# design.net
KiCad netlist of a schematic drawn in EasyEDA Pro
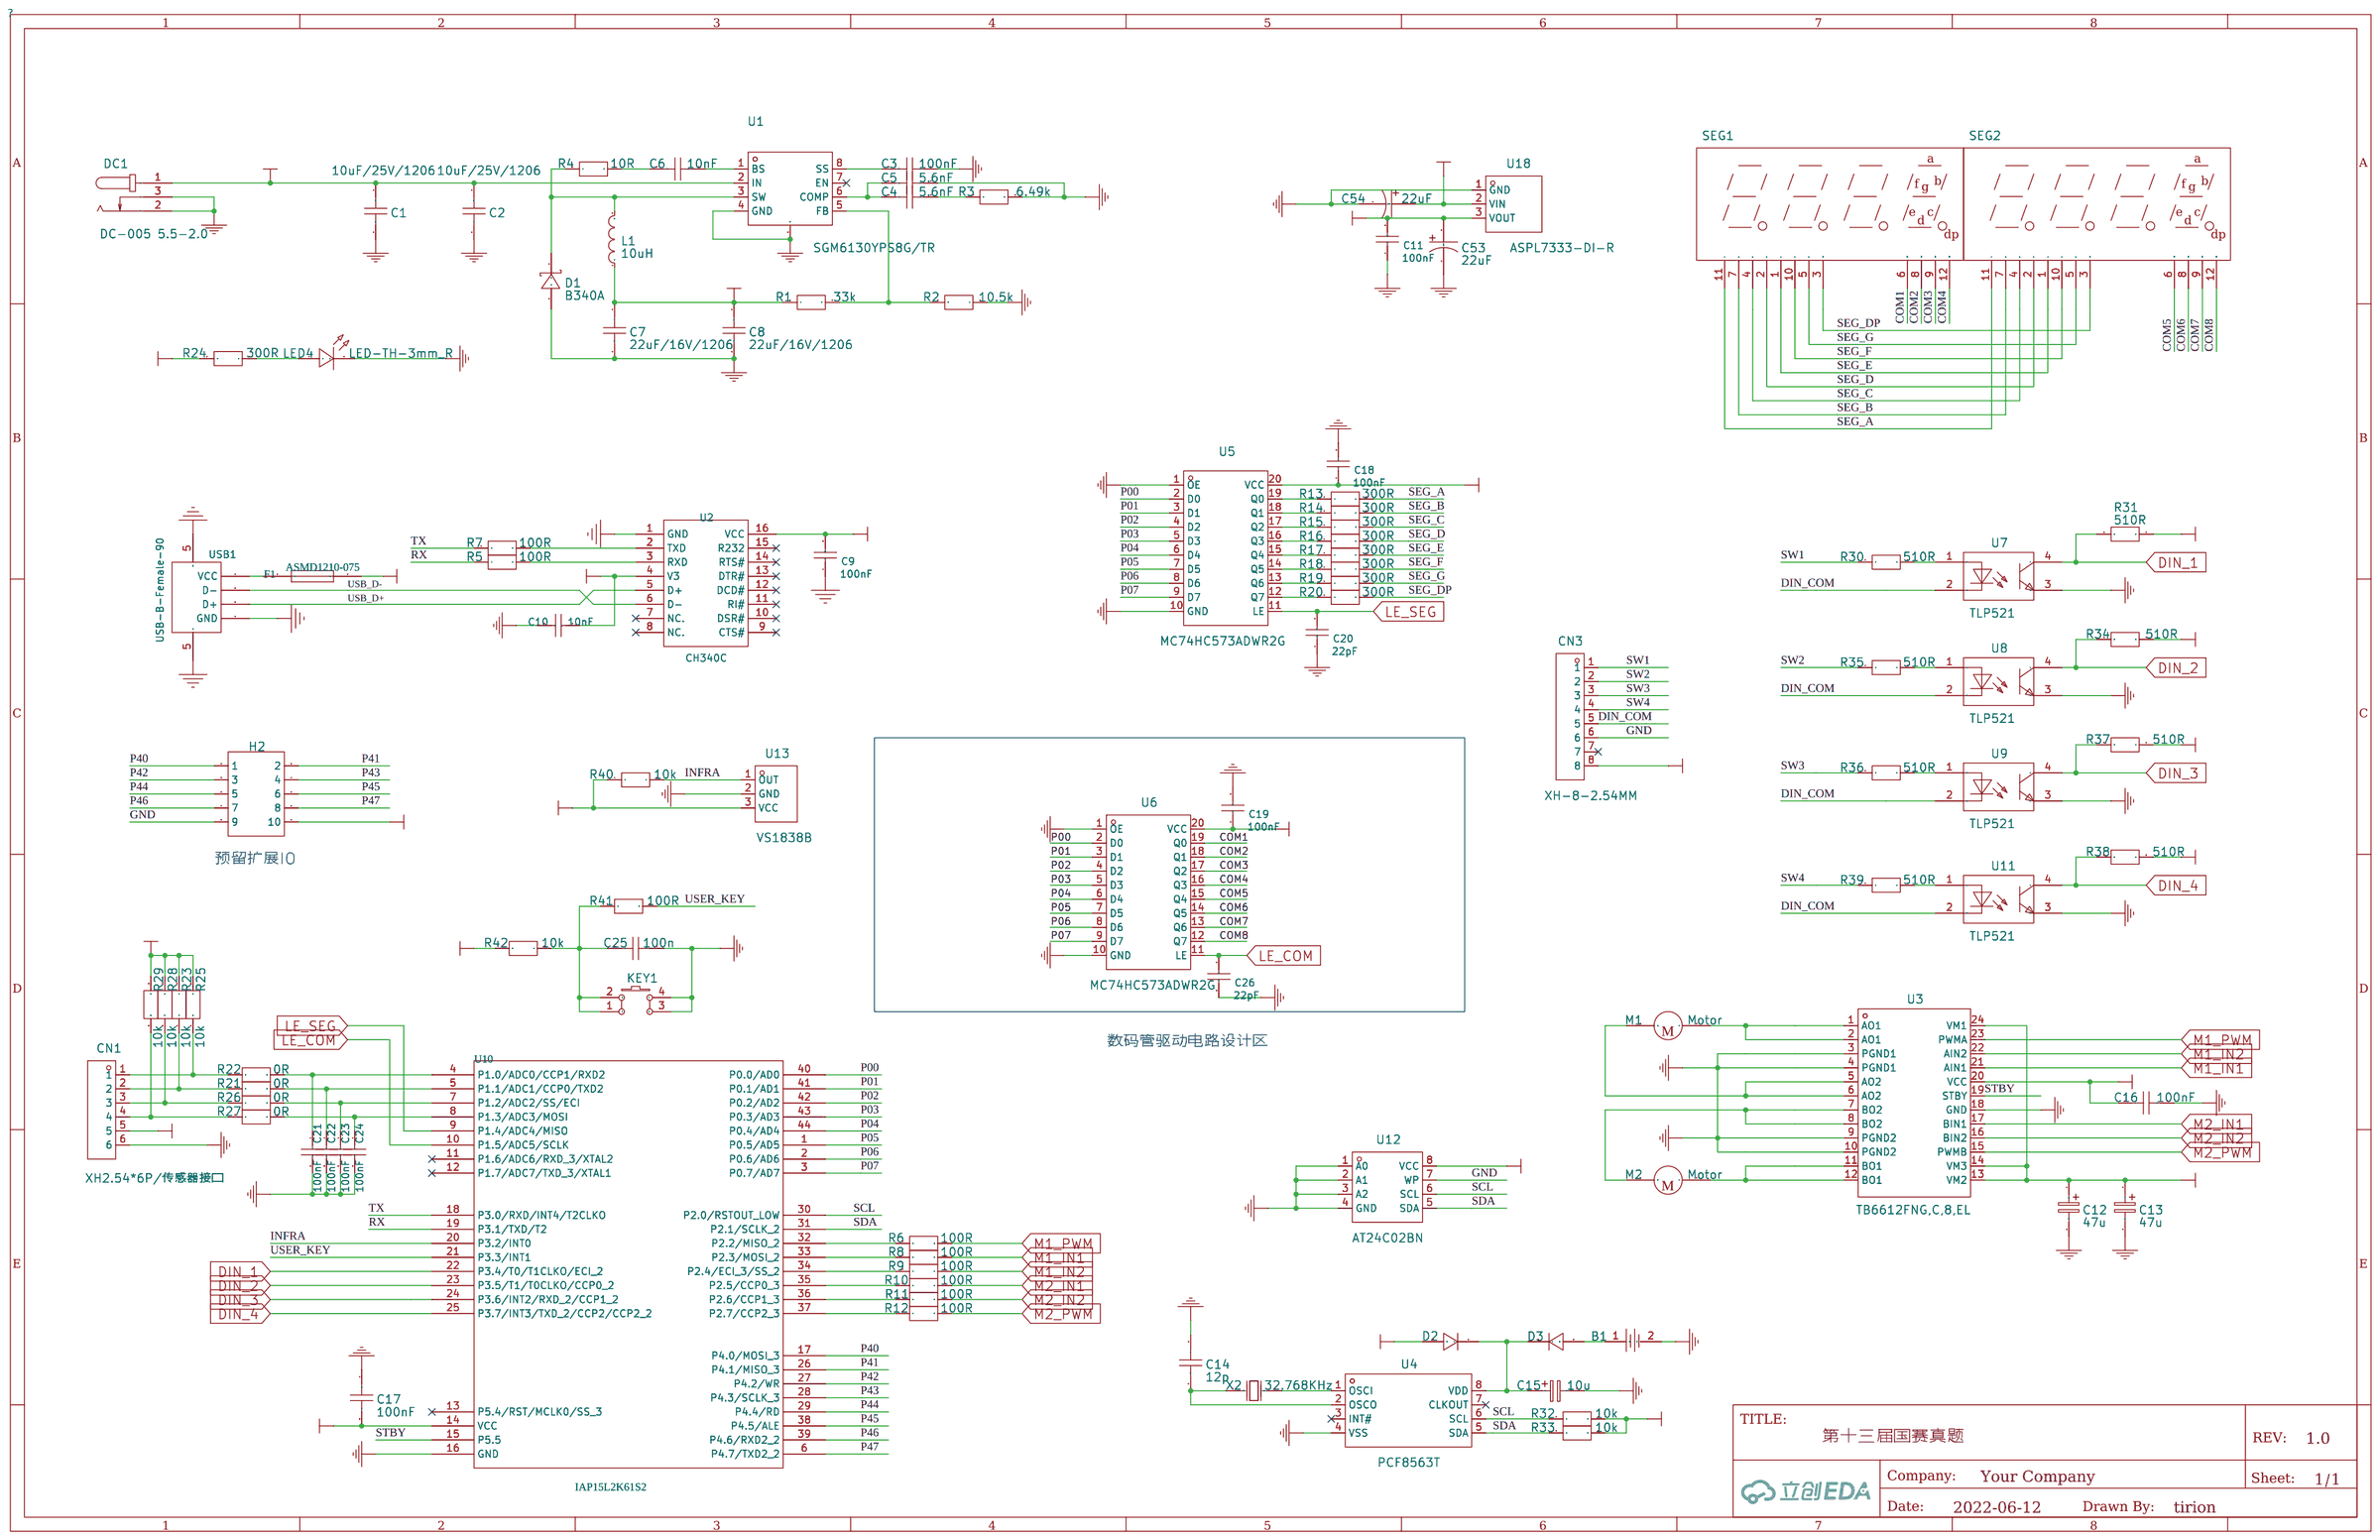
[diagram p0: schematic sheet]

(export (version "E")
  (design (tool "Eeschema 10.0.6"))
  (components
    (comp (ref "B1")
      (value "CR1220-2")
      (fields (field (name "Manufacturer") "Q&amp;J"))
      (libsource (lib "easyedapro") (part "CR1220-2"))
    )
    (comp (ref "C1") (value "10uF/25V/1206") (libsource (lib "easyedapro") (part "10uF/25V/1206")))
    (comp (ref "C2") (value "10uF/25V/1206") (libsource (lib "easyedapro") (part "10uF/25V/1206")))
    (comp (ref "C3") (value "100nF") (libsource (lib "") (part "100nF_1")))
    (comp (ref "C4") (value "5.6nF") (libsource (lib "easyedapro") (part "5.6nF")))
    (comp (ref "C5") (value "5.6nF") (libsource (lib "easyedapro") (part "5.6nF")))
    (comp (ref "C6") (value "10nF") (libsource (lib "easyedapro") (part "10nF")))
    (comp (ref "C7") (value "22uF/16V/1206") (libsource (lib "easyedapro") (part "22uF/16V/1206")))
    (comp (ref "C8") (value "22uF/16V/1206") (libsource (lib "easyedapro") (part "22uF/16V/1206")))
    (comp (ref "C9")
      (value "100nF")
      (fields (field (name "Manufacturer Part") "0805F104M500NT") (field (name "Manufacturer") "FH"))
      (libsource (lib "easyedapro") (part "100nF"))
    )
    (comp (ref "C10")
      (value "10nF")
      (fields (field (name "Manufacturer Part") "0805F104M500NT") (field (name "Manufacturer") "FH"))
      (libsource (lib "easyedapro") (part "100nF"))
    )
    (comp (ref "C11")
      (value "100nF")
      (fields (field (name "Manufacturer Part") "0805F104M500NT") (field (name "Manufacturer") "FH"))
      (libsource (lib "easyedapro") (part "100nF"))
    )
    (comp (ref "C12") (value "47u") (libsource (lib "easyedapro") (part "47u")))
    (comp (ref "C13") (value "47u") (libsource (lib "easyedapro") (part "47u")))
    (comp (ref "C14") (value "12p") (libsource (lib "easyedapro") (part "12p")))
    (comp (ref "C15") (value "10u") (libsource (lib "easyedapro") (part "10u")))
    (comp (ref "C16") (value "100nF") (libsource (lib "") (part "100nF_1")))
    (comp (ref "C17") (value "100nF") (libsource (lib "") (part "100nF_1")))
    (comp (ref "C18")
      (value "100nF")
      (fields (field (name "Manufacturer Part") "0805F104M500NT") (field (name "Manufacturer") "FH"))
      (libsource (lib "easyedapro") (part "100nF"))
    )
    (comp (ref "C19")
      (value "100nF")
      (fields (field (name "Manufacturer Part") "0805F104M500NT") (field (name "Manufacturer") "FH"))
      (libsource (lib "easyedapro") (part "100nF"))
    )
    (comp (ref "C20")
      (value "22pF")
      (fields (field (name "Manufacturer Part") "0805F104M500NT") (field (name "Manufacturer") "FH"))
      (libsource (lib "easyedapro") (part "100nF"))
    )
    (comp (ref "C21")
      (value "100nF")
      (fields (field (name "Manufacturer Part") "0805F104M500NT") (field (name "Manufacturer") "FH"))
      (libsource (lib "easyedapro") (part "100nF"))
    )
    (comp (ref "C22")
      (value "100nF")
      (fields (field (name "Manufacturer Part") "0805F104M500NT") (field (name "Manufacturer") "FH"))
      (libsource (lib "easyedapro") (part "100nF"))
    )
    (comp (ref "C23")
      (value "100nF")
      (fields (field (name "Manufacturer Part") "0805F104M500NT") (field (name "Manufacturer") "FH"))
      (libsource (lib "easyedapro") (part "100nF"))
    )
    (comp (ref "C24")
      (value "100nF")
      (fields (field (name "Manufacturer Part") "0805F104M500NT") (field (name "Manufacturer") "FH"))
      (libsource (lib "easyedapro") (part "100nF"))
    )
    (comp (ref "C25") (value "100n") (libsource (lib "easyedapro") (part "100n")))
    (comp (ref "C26")
      (value "22pF")
      (fields (field (name "Manufacturer Part") "0805F104M500NT") (field (name "Manufacturer") "FH"))
      (libsource (lib "easyedapro") (part "100nF"))
    )
    (comp (ref "C53")
      (value "22uF")
      (fields (field (name "Manufacturer") "HonorElec"))
      (libsource (lib "easyedapro") (part "22uF"))
    )
    (comp (ref "C54")
      (value "22uF")
      (fields (field (name "Manufacturer") "HonorElec"))
      (libsource (lib "easyedapro") (part "22uF"))
    )
    (comp (ref "CN1")
      (value "XH2.54*6P/传感器接口")
      (fields (field (name "Manufacturer Part") "XH2.54*6P_直插"))
      (libsource (lib "easyedapro") (part "XH2.54*6P/传感器接口"))
    )
    (comp (ref "CN3") (value "XH-8-2.54MM") (libsource (lib "easyedapro") (part "XH-8-2.54MM")))
    (comp (ref "D1")
      (value "B340A")
      (fields (field (name "Manufacturer") "MDD"))
      (libsource (lib "easyedapro") (part "B340A"))
    )
    (comp (ref "D2")
      (value "1N4148")
      (fields (field (name "Manufacturer") "STMicroelectronics"))
      (libsource (lib "easyedapro") (part "1N4148"))
    )
    (comp (ref "D3")
      (value "1N4148")
      (fields (field (name "Manufacturer") "STMicroelectronics"))
      (libsource (lib "easyedapro") (part "1N4148"))
    )
    (comp (ref "DC1")
      (value "DC-005 5.5-2.0")
      (fields (field (name "Manufacturer") "ShenzhenCankemeng"))
      (libsource (lib "easyedapro") (part "DC-005 5.5-2.0"))
    )
    (comp (ref "F1")
      (value "ASMD1210-075")
      (fields (field (name "Publisher") "Altium Limited"))
      (libsource (lib "easyedapro") (part "ASMD1210-075"))
    )
    (comp (ref "H2") (value "HDR-F-2.54_2x5") (libsource (lib "easyedapro") (part "HDR-F-2.54_2x5")))
    (comp (ref "KEY1")
      (value "K4-6×6_SMD")
      (fields (field (name "Manufacturer Part") "K2-6639SP-D4SC-04") (field (name "Manufacturer") "韩国韩荣"))
      (libsource (lib "easyedapro") (part "K4-6×6_SMD"))
    )
    (comp (ref "L1")
      (value "10uH")
      (fields
        (field (name "Manufacturer Part") "1217AS-H-100M=P3")
        (field (name "Manufacturer") "MurataElectronics")
      )
      (libsource (lib "easyedapro") (part "10uH"))
    )
    (comp (ref "LED4")
      (value "LED-TH-3mm_R")
      (fields
        (field (name "Manufacturer Part") "204-10SDRD/S530-A3-L")
        (field (name "Manufacturer") "EVERLIGHT(台湾亿光)")
      )
      (libsource (lib "easyedapro") (part "LED-TH-3mm_R"))
    )
    (comp (ref "M1") (value "Motor") (libsource (lib "easyedapro") (part "Motor")))
    (comp (ref "M2") (value "Motor") (libsource (lib "easyedapro") (part "Motor")))
    (comp (ref "R1") (value "33k") (libsource (lib "easyedapro") (part "33k")))
    (comp (ref "R2") (value "10.5k") (libsource (lib "easyedapro") (part "10.5k")))
    (comp (ref "R3") (value "6.49k") (libsource (lib "easyedapro") (part "6.49k")))
    (comp (ref "R4") (value "10R") (libsource (lib "easyedapro") (part "10R")))
    (comp (ref "R5") (value "100R") (libsource (lib "easyedapro") (part "100R")))
    (comp (ref "R6") (value "100R") (libsource (lib "easyedapro") (part "100R")))
    (comp (ref "R7") (value "100R") (libsource (lib "easyedapro") (part "100R")))
    (comp (ref "R8") (value "100R") (libsource (lib "easyedapro") (part "100R")))
    (comp (ref "R9") (value "100R") (libsource (lib "easyedapro") (part "100R")))
    (comp (ref "R10") (value "100R") (libsource (lib "easyedapro") (part "100R")))
    (comp (ref "R11") (value "100R") (libsource (lib "easyedapro") (part "100R")))
    (comp (ref "R12") (value "100R") (libsource (lib "easyedapro") (part "100R")))
    (comp (ref "R13") (value "300R") (libsource (lib "easyedapro") (part "300R")))
    (comp (ref "R14") (value "300R") (libsource (lib "easyedapro") (part "300R")))
    (comp (ref "R15") (value "300R") (libsource (lib "easyedapro") (part "300R")))
    (comp (ref "R16") (value "300R") (libsource (lib "easyedapro") (part "300R")))
    (comp (ref "R17") (value "300R") (libsource (lib "easyedapro") (part "300R")))
    (comp (ref "R18") (value "300R") (libsource (lib "easyedapro") (part "300R")))
    (comp (ref "R19") (value "300R") (libsource (lib "easyedapro") (part "300R")))
    (comp (ref "R20") (value "300R") (libsource (lib "easyedapro") (part "300R")))
    (comp (ref "R21") (value "0R") (libsource (lib "easyedapro") (part "0R")))
    (comp (ref "R22") (value "0R") (libsource (lib "easyedapro") (part "0R")))
    (comp (ref "R23") (value "10k") (libsource (lib "easyedapro") (part "10k")))
    (comp (ref "R24") (value "300R") (libsource (lib "easyedapro") (part "300R")))
    (comp (ref "R25") (value "10k") (libsource (lib "easyedapro") (part "10k")))
    (comp (ref "R26") (value "0R") (libsource (lib "easyedapro") (part "0R")))
    (comp (ref "R27") (value "0R") (libsource (lib "easyedapro") (part "0R")))
    (comp (ref "R28") (value "10k") (libsource (lib "easyedapro") (part "10k")))
    (comp (ref "R29") (value "10k") (libsource (lib "easyedapro") (part "10k")))
    (comp (ref "R30") (value "510R") (libsource (lib "easyedapro") (part "510R")))
    (comp (ref "R31") (value "510R") (libsource (lib "easyedapro") (part "510R")))
    (comp (ref "R32") (value "10k") (libsource (lib "easyedapro") (part "10k")))
    (comp (ref "R33") (value "10k") (libsource (lib "easyedapro") (part "10k")))
    (comp (ref "R34") (value "510R") (libsource (lib "easyedapro") (part "510R")))
    (comp (ref "R35") (value "510R") (libsource (lib "easyedapro") (part "510R")))
    (comp (ref "R36") (value "510R") (libsource (lib "easyedapro") (part "510R")))
    (comp (ref "R37") (value "510R") (libsource (lib "easyedapro") (part "510R")))
    (comp (ref "R38") (value "510R") (libsource (lib "easyedapro") (part "510R")))
    (comp (ref "R39") (value "510R") (libsource (lib "easyedapro") (part "510R")))
    (comp (ref "R40") (value "10k") (libsource (lib "easyedapro") (part "10k")))
    (comp (ref "R41") (value "100R") (libsource (lib "easyedapro") (part "100R")))
    (comp (ref "R42") (value "10k") (libsource (lib "easyedapro") (part "10k")))
    (comp (ref "SEG1")
      (value "0.36寸4位数码管")
      (fields (field (name "Manufacturer Part") "FJ5461BH纯红") (field (name "Manufacturer") "ReliaPro"))
      (libsource (lib "easyedapro") (part "0.36寸4位数码管"))
    )
    (comp (ref "SEG2")
      (value "0.36寸4位数码管")
      (fields (field (name "Manufacturer Part") "FJ5461BH纯红") (field (name "Manufacturer") "ReliaPro"))
      (libsource (lib "easyedapro") (part "0.36寸4位数码管"))
    )
    (comp (ref "U1")
      (value "SGM6130YPS8G/TR")
      (fields (field (name "Manufacturer") "SGMICRO"))
      (libsource (lib "easyedapro") (part "SGM6130YPS8G/TR"))
    )
    (comp (ref "U2")
      (value "CH340C")
      (fields (field (name "Manufacturer") "WCH"))
      (libsource (lib "easyedapro") (part "CH340C"))
    )
    (comp (ref "U3")
      (value "TB6612FNG,C,8,EL")
      (fields (field (name "Manufacturer") "TOSHIBA"))
      (libsource (lib "easyedapro") (part "TB6612FNG,C,8,EL"))
    )
    (comp (ref "U4")
      (value "PCF8563T")
      (fields (field (name "Manufacturer Part") "PCF8563T/5,518") (field (name "Manufacturer") "NXP"))
      (libsource (lib "easyedapro") (part "PCF8563T"))
    )
    (comp (ref "U5")
      (value "MC74HC573ADWR2G")
      (fields (field (name "Manufacturer") "ONSemicon"))
      (libsource (lib "easyedapro") (part "MC74HC573ADWR2G"))
    )
    (comp (ref "U6")
      (value "MC74HC573ADWR2G")
      (fields (field (name "Manufacturer") "ONSemicon"))
      (libsource (lib "easyedapro") (part "MC74HC573ADWR2G"))
    )
    (comp (ref "U7") (value "TLP521") (libsource (lib "easyedapro") (part "TLP521")))
    (comp (ref "U8") (value "TLP521") (libsource (lib "easyedapro") (part "TLP521")))
    (comp (ref "U9") (value "TLP521") (libsource (lib "easyedapro") (part "TLP521")))
    (comp (ref "U10") (value "IAP15L2K61S2") (libsource (lib "easyedapro") (part "IAP15L2K61S2")))
    (comp (ref "U11") (value "TLP521") (libsource (lib "easyedapro") (part "TLP521")))
    (comp (ref "U12") (value "AT24C02BN") (libsource (lib "easyedapro") (part "AT24C02BN")))
    (comp (ref "U13") (value "VS1838B") (libsource (lib "easyedapro") (part "VS1838B")))
    (comp (ref "U18")
      (value "ASPL7333-DI-R")
      (fields (field (name "Manufacturer") "Ascend(安森德)"))
      (libsource (lib "easyedapro") (part "ASPL7333-DI-R"))
    )
    (comp (ref "USB1")
      (value "USB-B-Female-90")
      (fields (field (name "Manufacturer Part") "USB-BF90") (field (name "Manufacturer") "ValuePro"))
      (libsource (lib "easyedapro") (part "USB-B-Female-90"))
    )
    (comp (ref "X2")
      (value "32.768KHz")
      (fields
        (field (name "Manufacturer Part") "6K832768F12UB")
        (field (name "Manufacturer") "SHENZHENCRYSTALTECH")
      )
      (libsource (lib "easyedapro") (part "32.768KHz"))
    )
  )
  (nets
    (net (code "1") (name "+3V3") (class "Default")
      (node (ref "C10") (pin "1") (pinfunction "1_1") (pintype "input"))
      (node (ref "C11") (pin "2") (pinfunction "2_2") (pintype "input"))
      (node (ref "C16") (pin "1") (pinfunction "1_1") (pintype "input"))
      (node (ref "C17") (pin "2") (pinfunction "2_2") (pintype "input"))
      (node (ref "C18") (pin "1") (pinfunction "1_1") (pintype "input"))
      (node (ref "C19") (pin "1") (pinfunction "1_1") (pintype "input"))
      (node (ref "C53") (pin "1") (pinfunction "1_1") (pintype "input"))
      (node (ref "C7") (pin "1") (pinfunction "1_1") (pintype "input"))
      (node (ref "C8") (pin "1") (pinfunction "1_1") (pintype "input"))
      (node (ref "C9") (pin "2") (pinfunction "2_2") (pintype "input"))
      (node (ref "CN1") (pin "5") (pinfunction "5_5") (pintype "input"))
      (node (ref "D2") (pin "2") (pinfunction "2_2") (pintype "input"))
      (node (ref "H2") (pin "10") (pinfunction "10_10") (pintype "input"))
      (node (ref "L1") (pin "1") (pinfunction "1_1") (pintype "input"))
      (node (ref "R1") (pin "1") (pinfunction "1_1") (pintype "input"))
      (node (ref "R23") (pin "1") (pinfunction "1_1") (pintype "input"))
      (node (ref "R24") (pin "2") (pinfunction "2_2") (pintype "input"))
      (node (ref "R25") (pin "1") (pinfunction "1_1") (pintype "input"))
      (node (ref "R28") (pin "1") (pinfunction "1_1") (pintype "input"))
      (node (ref "R29") (pin "1") (pinfunction "1_1") (pintype "input"))
      (node (ref "R31") (pin "1") (pinfunction "1_1") (pintype "input"))
      (node (ref "R32") (pin "2") (pinfunction "2_2") (pintype "input"))
      (node (ref "R33") (pin "2") (pinfunction "2_2") (pintype "input"))
      (node (ref "R34") (pin "1") (pinfunction "1_1") (pintype "input"))
      (node (ref "R37") (pin "1") (pinfunction "1_1") (pintype "input"))
      (node (ref "R38") (pin "1") (pinfunction "1_1") (pintype "input"))
      (node (ref "R40") (pin "1") (pinfunction "1_1") (pintype "input"))
      (node (ref "R42") (pin "2") (pinfunction "2_2") (pintype "input"))
      (node (ref "U10") (pin "14") (pinfunction "VCC_14") (pintype "input"))
      (node (ref "U12") (pin "8") (pinfunction "VCC_8") (pintype "input"))
      (node (ref "U13") (pin "3") (pinfunction "VCC_3") (pintype "input"))
      (node (ref "U18") (pin "3") (pinfunction "VOUT_3") (pintype "input"))
      (node (ref "U2") (pin "16") (pinfunction "VCC_16") (pintype "input"))
      (node (ref "U2") (pin "4") (pinfunction "V3_4") (pintype "input"))
      (node (ref "U3") (pin "20") (pinfunction "VCC_20") (pintype "input"))
      (node (ref "U5") (pin "20") (pinfunction "VCC_20") (pintype "input"))
      (node (ref "U6") (pin "20") (pinfunction "VCC_20") (pintype "input"))
    )
    (net (code "2") (name "/COM1") (class "Default")
      (node (ref "SEG1") (pin "6") (pinfunction "DIG4_6") (pintype "input"))
      (node (ref "U6") (pin "19") (pinfunction "Q0_19") (pintype "input"))
    )
    (net (code "3") (name "/COM2") (class "Default")
      (node (ref "SEG1") (pin "8") (pinfunction "DIG3_8") (pintype "input"))
      (node (ref "U6") (pin "18") (pinfunction "Q1_18") (pintype "input"))
    )
    (net (code "4") (name "/COM3") (class "Default")
      (node (ref "SEG1") (pin "9") (pinfunction "DIG2_9") (pintype "input"))
      (node (ref "U6") (pin "17") (pinfunction "Q2_17") (pintype "input"))
    )
    (net (code "5") (name "/COM4") (class "Default")
      (node (ref "SEG1") (pin "12") (pinfunction "DIG1_12") (pintype "input"))
      (node (ref "U6") (pin "16") (pinfunction "Q3_16") (pintype "input"))
    )
    (net (code "6") (name "/COM5") (class "Default")
      (node (ref "SEG2") (pin "6") (pinfunction "DIG4_6") (pintype "input"))
      (node (ref "U6") (pin "15") (pinfunction "Q4_15") (pintype "input"))
    )
    (net (code "7") (name "/COM6") (class "Default")
      (node (ref "SEG2") (pin "8") (pinfunction "DIG3_8") (pintype "input"))
      (node (ref "U6") (pin "14") (pinfunction "Q5_14") (pintype "input"))
    )
    (net (code "8") (name "/COM7") (class "Default")
      (node (ref "SEG2") (pin "9") (pinfunction "DIG2_9") (pintype "input"))
      (node (ref "U6") (pin "13") (pinfunction "Q6_13") (pintype "input"))
    )
    (net (code "9") (name "/COM8") (class "Default")
      (node (ref "SEG2") (pin "12") (pinfunction "DIG1_12") (pintype "input"))
      (node (ref "U6") (pin "12") (pinfunction "Q7_12") (pintype "input"))
    )
    (net (code "10") (name "/DIN_COM") (class "Default")
      (node (ref "CN3") (pin "5") (pinfunction "5_5") (pintype "input"))
      (node (ref "U11") (pin "2") (pinfunction "2_2") (pintype "input"))
      (node (ref "U7") (pin "2") (pinfunction "2_2") (pintype "input"))
      (node (ref "U8") (pin "2") (pinfunction "2_2") (pintype "input"))
      (node (ref "U9") (pin "2") (pinfunction "2_2") (pintype "input"))
    )
    (net (code "11") (name "/INFRA") (class "Default")
      (node (ref "R40") (pin "2") (pinfunction "2_2") (pintype "input"))
      (node (ref "U10") (pin "20") (pinfunction "P3.2/INT0_20") (pintype "input"))
      (node (ref "U13") (pin "1") (pinfunction "OUT_1") (pintype "input"))
    )
    (net (code "12") (name "/P00") (class "Default")
      (node (ref "U10") (pin "40") (pinfunction "P0.0/AD0_40") (pintype "bidirectional"))
      (node (ref "U5") (pin "2") (pinfunction "D0_2") (pintype "input"))
      (node (ref "U6") (pin "2") (pinfunction "D0_2") (pintype "input"))
    )
    (net (code "13") (name "/P01") (class "Default")
      (node (ref "U10") (pin "41") (pinfunction "P0.1/AD1_41") (pintype "bidirectional"))
      (node (ref "U5") (pin "3") (pinfunction "D1_3") (pintype "input"))
      (node (ref "U6") (pin "3") (pinfunction "D1_3") (pintype "input"))
    )
    (net (code "14") (name "/P02") (class "Default")
      (node (ref "U10") (pin "42") (pinfunction "P0.2/AD2_42") (pintype "bidirectional"))
      (node (ref "U5") (pin "4") (pinfunction "D2_4") (pintype "input"))
      (node (ref "U6") (pin "4") (pinfunction "D2_4") (pintype "input"))
    )
    (net (code "15") (name "/P03") (class "Default")
      (node (ref "U10") (pin "43") (pinfunction "P0.3/AD3_43") (pintype "bidirectional"))
      (node (ref "U5") (pin "5") (pinfunction "D3_5") (pintype "input"))
      (node (ref "U6") (pin "5") (pinfunction "D3_5") (pintype "input"))
    )
    (net (code "16") (name "/P04") (class "Default")
      (node (ref "U10") (pin "44") (pinfunction "P0.4/AD4_44") (pintype "bidirectional"))
      (node (ref "U5") (pin "6") (pinfunction "D4_6") (pintype "input"))
      (node (ref "U6") (pin "6") (pinfunction "D4_6") (pintype "input"))
    )
    (net (code "17") (name "/P05") (class "Default")
      (node (ref "U10") (pin "1") (pinfunction "P0.5/AD5_1") (pintype "bidirectional"))
      (node (ref "U5") (pin "7") (pinfunction "D5_7") (pintype "input"))
      (node (ref "U6") (pin "7") (pinfunction "D5_7") (pintype "input"))
    )
    (net (code "18") (name "/P06") (class "Default")
      (node (ref "U10") (pin "2") (pinfunction "P0.6/AD6_2") (pintype "bidirectional"))
      (node (ref "U5") (pin "8") (pinfunction "D6_8") (pintype "input"))
      (node (ref "U6") (pin "8") (pinfunction "D6_8") (pintype "input"))
    )
    (net (code "19") (name "/P07") (class "Default")
      (node (ref "U10") (pin "3") (pinfunction "P0.7/AD7_3") (pintype "bidirectional"))
      (node (ref "U5") (pin "9") (pinfunction "D7_9") (pintype "input"))
      (node (ref "U6") (pin "9") (pinfunction "D7_9") (pintype "input"))
    )
    (net (code "20") (name "/P40") (class "Default")
      (node (ref "H2") (pin "1") (pinfunction "1_1") (pintype "input"))
      (node (ref "U10") (pin "17") (pinfunction "P4.0/MOSI_3_17") (pintype "bidirectional"))
    )
    (net (code "21") (name "/P41") (class "Default")
      (node (ref "H2") (pin "2") (pinfunction "2_2") (pintype "input"))
      (node (ref "U10") (pin "26") (pinfunction "P4.1/MISO_3_26") (pintype "bidirectional"))
    )
    (net (code "22") (name "/P42") (class "Default")
      (node (ref "H2") (pin "3") (pinfunction "3_3") (pintype "input"))
      (node (ref "U10") (pin "27") (pinfunction "P4.2/WR_27") (pintype "input"))
    )
    (net (code "23") (name "/P43") (class "Default")
      (node (ref "H2") (pin "4") (pinfunction "4_4") (pintype "input"))
      (node (ref "U10") (pin "28") (pinfunction "P4.3/SCLK_3_28") (pintype "bidirectional"))
    )
    (net (code "24") (name "/P44") (class "Default")
      (node (ref "H2") (pin "5") (pinfunction "5_5") (pintype "input"))
      (node (ref "U10") (pin "29") (pinfunction "P4.4/RD_29") (pintype "input"))
    )
    (net (code "25") (name "/P45") (class "Default")
      (node (ref "H2") (pin "6") (pinfunction "6_6") (pintype "input"))
      (node (ref "U10") (pin "38") (pinfunction "P4.5/ALE_38") (pintype "input"))
    )
    (net (code "26") (name "/P46") (class "Default")
      (node (ref "H2") (pin "7") (pinfunction "7_7") (pintype "input"))
      (node (ref "U10") (pin "39") (pinfunction "P4.6/RXD2_2_39") (pintype "input"))
    )
    (net (code "27") (name "/P47") (class "Default")
      (node (ref "H2") (pin "8") (pinfunction "8_8") (pintype "input"))
      (node (ref "U10") (pin "6") (pinfunction "P4.7/TXD2_2_6") (pintype "bidirectional"))
    )
    (net (code "28") (name "/RX") (class "Default")
      (node (ref "R5") (pin "1") (pinfunction "1_1") (pintype "input"))
      (node (ref "U10") (pin "19") (pinfunction "P3.1/TXD/T2_19") (pintype "input"))
    )
    (net (code "29") (name "/SCL") (class "Default")
      (node (ref "R32") (pin "1") (pinfunction "1_1") (pintype "input"))
      (node (ref "U10") (pin "30") (pinfunction "P2.0/RSTOUT_LOW_30") (pintype "bidirectional"))
      (node (ref "U12") (pin "6") (pinfunction "SCL_6") (pintype "input"))
      (node (ref "U4") (pin "6") (pinfunction "SCL_6") (pintype "input"))
    )
    (net (code "30") (name "/SDA") (class "Default")
      (node (ref "R33") (pin "1") (pinfunction "1_1") (pintype "input"))
      (node (ref "U10") (pin "31") (pinfunction "P2.1/SCLK_2_31") (pintype "bidirectional"))
      (node (ref "U12") (pin "5") (pinfunction "SDA_5") (pintype "input"))
      (node (ref "U4") (pin "5") (pinfunction "SDA_5") (pintype "input"))
    )
    (net (code "31") (name "/SEG_A") (class "Default")
      (node (ref "R13") (pin "2") (pinfunction "2_2") (pintype "input"))
      (node (ref "SEG1") (pin "11") (pinfunction "A_11") (pintype "input"))
      (node (ref "SEG2") (pin "11") (pinfunction "A_11") (pintype "input"))
    )
    (net (code "32") (name "/SEG_B") (class "Default")
      (node (ref "R14") (pin "2") (pinfunction "2_2") (pintype "input"))
      (node (ref "SEG1") (pin "7") (pinfunction "B_7") (pintype "input"))
      (node (ref "SEG2") (pin "7") (pinfunction "B_7") (pintype "input"))
    )
    (net (code "33") (name "/SEG_C") (class "Default")
      (node (ref "R15") (pin "2") (pinfunction "2_2") (pintype "input"))
      (node (ref "SEG1") (pin "4") (pinfunction "C_4") (pintype "input"))
      (node (ref "SEG2") (pin "4") (pinfunction "C_4") (pintype "input"))
    )
    (net (code "34") (name "/SEG_D") (class "Default")
      (node (ref "R16") (pin "2") (pinfunction "2_2") (pintype "input"))
      (node (ref "SEG1") (pin "2") (pinfunction "D_2") (pintype "input"))
      (node (ref "SEG2") (pin "2") (pinfunction "D_2") (pintype "input"))
    )
    (net (code "35") (name "/SEG_DP") (class "Default")
      (node (ref "R20") (pin "2") (pinfunction "2_2") (pintype "input"))
      (node (ref "SEG1") (pin "3") (pinfunction "DP_3") (pintype "input"))
      (node (ref "SEG2") (pin "3") (pinfunction "DP_3") (pintype "input"))
    )
    (net (code "36") (name "/SEG_E") (class "Default")
      (node (ref "R17") (pin "2") (pinfunction "2_2") (pintype "input"))
      (node (ref "SEG1") (pin "1") (pinfunction "E_1") (pintype "input"))
      (node (ref "SEG2") (pin "1") (pinfunction "E_1") (pintype "input"))
    )
    (net (code "37") (name "/SEG_F") (class "Default")
      (node (ref "R18") (pin "2") (pinfunction "2_2") (pintype "input"))
      (node (ref "SEG1") (pin "10") (pinfunction "F_10") (pintype "input"))
      (node (ref "SEG2") (pin "10") (pinfunction "F_10") (pintype "input"))
    )
    (net (code "38") (name "/SEG_G") (class "Default")
      (node (ref "R19") (pin "2") (pinfunction "2_2") (pintype "input"))
      (node (ref "SEG1") (pin "5") (pinfunction "G_5") (pintype "input"))
      (node (ref "SEG2") (pin "5") (pinfunction "G_5") (pintype "input"))
    )
    (net (code "39") (name "/STBY") (class "Default")
      (node (ref "U10") (pin "15") (pinfunction "P5.5_15") (pintype "input"))
      (node (ref "U3") (pin "19") (pinfunction "STBY_19") (pintype "input"))
    )
    (net (code "40") (name "/SW1") (class "Default")
      (node (ref "CN3") (pin "1") (pinfunction "1_1") (pintype "input"))
      (node (ref "R30") (pin "1") (pinfunction "1_1") (pintype "input"))
    )
    (net (code "41") (name "/SW2") (class "Default")
      (node (ref "CN3") (pin "2") (pinfunction "2_2") (pintype "input"))
      (node (ref "R35") (pin "1") (pinfunction "1_1") (pintype "input"))
    )
    (net (code "42") (name "/SW3") (class "Default")
      (node (ref "CN3") (pin "3") (pinfunction "3_3") (pintype "input"))
      (node (ref "R36") (pin "1") (pinfunction "1_1") (pintype "input"))
    )
    (net (code "43") (name "/SW4") (class "Default")
      (node (ref "CN3") (pin "4") (pinfunction "4_4") (pintype "input"))
      (node (ref "R39") (pin "1") (pinfunction "1_1") (pintype "input"))
    )
    (net (code "44") (name "/TX") (class "Default")
      (node (ref "R7") (pin "1") (pinfunction "1_1") (pintype "input"))
      (node (ref "U10") (pin "18") (pinfunction "P3.0/RXD/INT4/T2CLKO_18") (pintype "input"))
    )
    (net (code "45") (name "/USB_D+") (class "Default")
      (node (ref "U2") (pin "5") (pinfunction "D+_5") (pintype "input"))
      (node (ref "USB1") (pin "3") (pinfunction "D+_3") (pintype "input"))
    )
    (net (code "46") (name "/USB_D-") (class "Default")
      (node (ref "U2") (pin "6") (pinfunction "D-_6") (pintype "input"))
      (node (ref "USB1") (pin "2") (pinfunction "D-_2") (pintype "input"))
    )
    (net (code "47") (name "/USER_KEY") (class "Default")
      (node (ref "R41") (pin "1") (pinfunction "1_1") (pintype "input"))
      (node (ref "U10") (pin "21") (pinfunction "P3.3/INT1_21") (pintype "input"))
    )
    (net (code "48") (name "DC_IN") (class "Default")
      (node (ref "C1") (pin "2") (pinfunction "2_2") (pintype "input"))
      (node (ref "C12") (pin "1") (pinfunction "1_1") (pintype "input"))
      (node (ref "C13") (pin "1") (pinfunction "1_1") (pintype "input"))
      (node (ref "C2") (pin "2") (pinfunction "2_2") (pintype "input"))
      (node (ref "CN3") (pin "8") (pinfunction "8_8") (pintype "input"))
      (node (ref "DC1") (pin "1") (pinfunction "1_1") (pintype "input"))
      (node (ref "U1") (pin "2") (pinfunction "IN_2") (pintype "input"))
      (node (ref "U3") (pin "13") (pinfunction "VM2_13") (pintype "input"))
      (node (ref "U3") (pin "14") (pinfunction "VM3_14") (pintype "input"))
      (node (ref "U3") (pin "24") (pinfunction "VM1_24") (pintype "input"))
    )
    (net (code "49") (name "DIN_1") (class "Default")
      (node (ref "R31") (pin "2") (pinfunction "2_2") (pintype "input"))
      (node (ref "U10") (pin "22") (pinfunction "P3.4/T0/T1CLKO/ECI_2_22") (pintype "bidirectional"))
      (node (ref "U7") (pin "4") (pinfunction "4_4") (pintype "input"))
    )
    (net (code "50") (name "DIN_2") (class "Default")
      (node (ref "R34") (pin "2") (pinfunction "2_2") (pintype "input"))
      (node (ref "U10") (pin "23") (pinfunction "P3.5/T1/T0CLKO/CCP0_2_23") (pintype "input"))
      (node (ref "U8") (pin "4") (pinfunction "4_4") (pintype "input"))
    )
    (net (code "51") (name "DIN_3") (class "Default")
      (node (ref "R37") (pin "2") (pinfunction "2_2") (pintype "input"))
      (node (ref "U10") (pin "24") (pinfunction "P3.6/INT2/RXD_2/CCP1_2_24") (pintype "input"))
      (node (ref "U9") (pin "4") (pinfunction "4_4") (pintype "input"))
    )
    (net (code "52") (name "DIN_4") (class "Default")
      (node (ref "R38") (pin "2") (pinfunction "2_2") (pintype "input"))
      (node (ref "U10") (pin "25") (pinfunction "P3.7/INT3/TXD_2/CCP2/CCP2_2_25") (pintype "input"))
      (node (ref "U11") (pin "4") (pinfunction "4_4") (pintype "input"))
    )
    (net (code "53") (name "GND") (class "Default")
      (node (ref "B1") (pin "2") (pinfunction "2_2") (pintype "input"))
      (node (ref "C1") (pin "1") (pinfunction "1_1") (pintype "input"))
      (node (ref "C10") (pin "2") (pinfunction "2_2") (pintype "input"))
      (node (ref "C11") (pin "1") (pinfunction "1_1") (pintype "input"))
      (node (ref "C12") (pin "2") (pinfunction "2_2") (pintype "input"))
      (node (ref "C13") (pin "2") (pinfunction "2_2") (pintype "input"))
      (node (ref "C14") (pin "1") (pinfunction "1_1") (pintype "input"))
      (node (ref "C15") (pin "2") (pinfunction "2_2") (pintype "input"))
      (node (ref "C16") (pin "2") (pinfunction "2_2") (pintype "input"))
      (node (ref "C17") (pin "1") (pinfunction "1_1") (pintype "input"))
      (node (ref "C18") (pin "2") (pinfunction "2_2") (pintype "input"))
      (node (ref "C19") (pin "2") (pinfunction "2_2") (pintype "input"))
      (node (ref "C2") (pin "1") (pinfunction "1_1") (pintype "input"))
      (node (ref "C20") (pin "1") (pinfunction "1_1") (pintype "input"))
      (node (ref "C21") (pin "2") (pinfunction "2_2") (pintype "input"))
      (node (ref "C22") (pin "2") (pinfunction "2_2") (pintype "input"))
      (node (ref "C23") (pin "2") (pinfunction "2_2") (pintype "input"))
      (node (ref "C24") (pin "2") (pinfunction "2_2") (pintype "input"))
      (node (ref "C25") (pin "2") (pinfunction "2_2") (pintype "input"))
      (node (ref "C26") (pin "1") (pinfunction "1_1") (pintype "input"))
      (node (ref "C3") (pin "1") (pinfunction "1_1") (pintype "input"))
      (node (ref "C5") (pin "1") (pinfunction "1_1") (pintype "input"))
      (node (ref "C53") (pin "2") (pinfunction "2_2") (pintype "input"))
      (node (ref "C54") (pin "2") (pinfunction "2_2") (pintype "input"))
      (node (ref "C7") (pin "2") (pinfunction "2_2") (pintype "input"))
      (node (ref "C8") (pin "2") (pinfunction "2_2") (pintype "input"))
      (node (ref "C9") (pin "1") (pinfunction "1_1") (pintype "input"))
      (node (ref "CN1") (pin "6") (pinfunction "6_6") (pintype "input"))
      (node (ref "CN3") (pin "6") (pinfunction "6_6") (pintype "input"))
      (node (ref "D1") (pin "2") (pinfunction "A_2") (pintype "input"))
      (node (ref "DC1") (pin "2") (pinfunction "2_2") (pintype "input"))
      (node (ref "DC1") (pin "3") (pinfunction "3_3") (pintype "input"))
      (node (ref "H2") (pin "9") (pinfunction "9_9") (pintype "input"))
      (node (ref "KEY1") (pin "3") (pinfunction "3_3") (pintype "input"))
      (node (ref "KEY1") (pin "4") (pinfunction "4_4") (pintype "input"))
      (node (ref "LED4") (pin "2") (pinfunction "2_2") (pintype "input"))
      (node (ref "R2") (pin "1") (pinfunction "1_1") (pintype "input"))
      (node (ref "R3") (pin "2") (pinfunction "2_2") (pintype "input"))
      (node (ref "U1") (pin "4") (pinfunction "GND_4") (pintype "input"))
      (node (ref "U1") (pin "9") (pinfunction "9_9") (pintype "input"))
      (node (ref "U10") (pin "16") (pinfunction "GND_16") (pintype "input"))
      (node (ref "U11") (pin "3") (pinfunction "3_3") (pintype "input"))
      (node (ref "U12") (pin "1") (pinfunction "A0_1") (pintype "input"))
      (node (ref "U12") (pin "2") (pinfunction "A1_2") (pintype "input"))
      (node (ref "U12") (pin "3") (pinfunction "A2_3") (pintype "input"))
      (node (ref "U12") (pin "4") (pinfunction "GND_4") (pintype "input"))
      (node (ref "U12") (pin "7") (pinfunction "WP_7") (pintype "input"))
      (node (ref "U13") (pin "2") (pinfunction "GND_2") (pintype "input"))
      (node (ref "U18") (pin "1") (pinfunction "GND_1") (pintype "input"))
      (node (ref "U2") (pin "1") (pinfunction "GND_1") (pintype "input"))
      (node (ref "U3") (pin "10") (pinfunction "PGND2_10") (pintype "input"))
      (node (ref "U3") (pin "18") (pinfunction "GND_18") (pintype "input"))
      (node (ref "U3") (pin "3") (pinfunction "PGND1_3") (pintype "input"))
      (node (ref "U3") (pin "4") (pinfunction "PGND1_4") (pintype "input"))
      (node (ref "U3") (pin "9") (pinfunction "PGND2_9") (pintype "input"))
      (node (ref "U4") (pin "4") (pinfunction "VSS_4") (pintype "input"))
      (node (ref "U5") (pin "1") (pinfunction "OE_1") (pintype "input"))
      (node (ref "U5") (pin "10") (pinfunction "GND_10") (pintype "input"))
      (node (ref "U6") (pin "1") (pinfunction "OE_1") (pintype "input"))
      (node (ref "U6") (pin "10") (pinfunction "GND_10") (pintype "input"))
      (node (ref "U7") (pin "3") (pinfunction "3_3") (pintype "input"))
      (node (ref "U8") (pin "3") (pinfunction "3_3") (pintype "input"))
      (node (ref "U9") (pin "3") (pinfunction "3_3") (pintype "input"))
      (node (ref "USB1") (pin "4") (pinfunction "GND_4") (pintype "input"))
      (node (ref "USB1") (pin "5") (pinfunction "SH2_5") (pintype "input"))
    )
    (net (code "54") (name "LE_COM") (class "Default")
      (node (ref "C26") (pin "2") (pinfunction "2_2") (pintype "input"))
      (node (ref "U10") (pin "10") (pinfunction "P1.5/ADC5/SCLK_10") (pintype "input"))
      (node (ref "U6") (pin "11") (pinfunction "LE_11") (pintype "input"))
    )
    (net (code "55") (name "LE_SEG") (class "Default")
      (node (ref "C20") (pin "2") (pinfunction "2_2") (pintype "input"))
      (node (ref "U10") (pin "9") (pinfunction "P1.4/ADC4/MISO_9") (pintype "input"))
      (node (ref "U5") (pin "11") (pinfunction "LE_11") (pintype "input"))
    )
    (net (code "56") (name "M1_IN1") (class "Default")
      (node (ref "R8") (pin "2") (pinfunction "2_2") (pintype "input"))
      (node (ref "U3") (pin "21") (pinfunction "AIN1_21") (pintype "input"))
    )
    (net (code "57") (name "M1_IN2") (class "Default")
      (node (ref "R9") (pin "2") (pinfunction "2_2") (pintype "input"))
      (node (ref "U3") (pin "22") (pinfunction "AIN2_22") (pintype "input"))
    )
    (net (code "58") (name "M1_PWM") (class "Default")
      (node (ref "R6") (pin "2") (pinfunction "2_2") (pintype "input"))
      (node (ref "U3") (pin "23") (pinfunction "PWMA_23") (pintype "input"))
    )
    (net (code "59") (name "M2_IN1") (class "Default")
      (node (ref "R10") (pin "2") (pinfunction "2_2") (pintype "input"))
      (node (ref "U3") (pin "17") (pinfunction "BIN1_17") (pintype "input"))
    )
    (net (code "60") (name "M2_IN2") (class "Default")
      (node (ref "R11") (pin "2") (pinfunction "2_2") (pintype "input"))
      (node (ref "U3") (pin "16") (pinfunction "BIN2_16") (pintype "input"))
    )
    (net (code "61") (name "M2_PWM") (class "Default")
      (node (ref "R12") (pin "2") (pinfunction "2_2") (pintype "input"))
      (node (ref "U3") (pin "15") (pinfunction "PWMB_15") (pintype "input"))
    )
    (net (code "62") (name "Net-(B1-Pad1)") (class "Default")
      (node (ref "B1") (pin "1") (pinfunction "1_1") (pintype "input"))
      (node (ref "D3") (pin "2") (pinfunction "2_2") (pintype "input"))
    )
    (net (code "63") (name "Net-(C4-Pad1)") (class "Default")
      (node (ref "C4") (pin "1") (pinfunction "1_1") (pintype "input"))
      (node (ref "R3") (pin "1") (pinfunction "1_1") (pintype "input"))
    )
    (net (code "64") (name "Net-(C6-Pad2)") (class "Default")
      (node (ref "C6") (pin "2") (pinfunction "2_2") (pintype "input"))
      (node (ref "R4") (pin "2") (pinfunction "2_2") (pintype "input"))
    )
    (net (code "65") (name "Net-(C25-Pad1)") (class "Default")
      (node (ref "C25") (pin "1") (pinfunction "1_1") (pintype "input"))
      (node (ref "KEY1") (pin "1") (pinfunction "1_1") (pintype "input"))
      (node (ref "KEY1") (pin "2") (pinfunction "2_2") (pintype "input"))
      (node (ref "R41") (pin "2") (pinfunction "2_2") (pintype "input"))
      (node (ref "R42") (pin "1") (pinfunction "1_1") (pintype "input"))
    )
    (net (code "66") (name "Net-(CN1-Pad1)") (class "Default")
      (node (ref "CN1") (pin "1") (pinfunction "1_1") (pintype "input"))
      (node (ref "R22") (pin "1") (pinfunction "1_1") (pintype "input"))
      (node (ref "R25") (pin "2") (pinfunction "2_2") (pintype "input"))
    )
    (net (code "67") (name "Net-(CN1-Pad2)") (class "Default")
      (node (ref "CN1") (pin "2") (pinfunction "2_2") (pintype "input"))
      (node (ref "R21") (pin "1") (pinfunction "1_1") (pintype "input"))
      (node (ref "R23") (pin "2") (pinfunction "2_2") (pintype "input"))
    )
    (net (code "68") (name "Net-(CN1-Pad3)") (class "Default")
      (node (ref "CN1") (pin "3") (pinfunction "3_3") (pintype "input"))
      (node (ref "R26") (pin "1") (pinfunction "1_1") (pintype "input"))
      (node (ref "R28") (pin "2") (pinfunction "2_2") (pintype "input"))
    )
    (net (code "69") (name "Net-(CN1-Pad4)") (class "Default")
      (node (ref "CN1") (pin "4") (pinfunction "4_4") (pintype "input"))
      (node (ref "R27") (pin "1") (pinfunction "1_1") (pintype "input"))
      (node (ref "R29") (pin "2") (pinfunction "2_2") (pintype "input"))
    )
    (net (code "70") (name "Net-(D1-K)") (class "Default")
      (node (ref "D1") (pin "1") (pinfunction "K_1") (pintype "input"))
      (node (ref "L1") (pin "2") (pinfunction "2_2") (pintype "input"))
      (node (ref "R4") (pin "1") (pinfunction "1_1") (pintype "input"))
      (node (ref "U1") (pin "3") (pinfunction "SW_3") (pintype "input"))
    )
    (net (code "71") (name "Net-(LED4-Pad1)") (class "Default")
      (node (ref "LED4") (pin "1") (pinfunction "1_1") (pintype "input"))
      (node (ref "R24") (pin "1") (pinfunction "1_1") (pintype "input"))
    )
    (net (code "72") (name "Net-(M1-Pad1)") (class "Default")
      (node (ref "M1") (pin "1") (pinfunction "1_1") (pintype "input"))
      (node (ref "U3") (pin "1") (pinfunction "AO1_1") (pintype "input"))
      (node (ref "U3") (pin "2") (pinfunction "AO1_2") (pintype "input"))
    )
    (net (code "73") (name "Net-(M1-Pad2)") (class "Default")
      (node (ref "M1") (pin "2") (pinfunction "2_2") (pintype "input"))
      (node (ref "U3") (pin "5") (pinfunction "AO2_5") (pintype "input"))
      (node (ref "U3") (pin "6") (pinfunction "AO2_6") (pintype "input"))
    )
    (net (code "74") (name "Net-(M2-Pad1)") (class "Default")
      (node (ref "M2") (pin "1") (pinfunction "1_1") (pintype "input"))
      (node (ref "U3") (pin "11") (pinfunction "BO1_11") (pintype "input"))
      (node (ref "U3") (pin "12") (pinfunction "BO1_12") (pintype "input"))
    )
    (net (code "75") (name "Net-(M2-Pad2)") (class "Default")
      (node (ref "M2") (pin "2") (pinfunction "2_2") (pintype "input"))
      (node (ref "U3") (pin "7") (pinfunction "BO2_7") (pintype "input"))
      (node (ref "U3") (pin "8") (pinfunction "BO2_8") (pintype "input"))
    )
    (net (code "76") (name "Net-(R30-Pad2)") (class "Default")
      (node (ref "R30") (pin "2") (pinfunction "2_2") (pintype "input"))
      (node (ref "U7") (pin "1") (pinfunction "1_1") (pintype "input"))
    )
    (net (code "77") (name "Net-(R35-Pad2)") (class "Default")
      (node (ref "R35") (pin "2") (pinfunction "2_2") (pintype "input"))
      (node (ref "U8") (pin "1") (pinfunction "1_1") (pintype "input"))
    )
    (net (code "78") (name "Net-(R36-Pad2)") (class "Default")
      (node (ref "R36") (pin "2") (pinfunction "2_2") (pintype "input"))
      (node (ref "U9") (pin "1") (pinfunction "1_1") (pintype "input"))
    )
    (net (code "79") (name "Net-(R39-Pad2)") (class "Default")
      (node (ref "R39") (pin "2") (pinfunction "2_2") (pintype "input"))
      (node (ref "U11") (pin "1") (pinfunction "1_1") (pintype "input"))
    )
    (net (code "80") (name "Net-(U1-BS)") (class "Default")
      (node (ref "C6") (pin "1") (pinfunction "1_1") (pintype "input"))
      (node (ref "U1") (pin "1") (pinfunction "BS_1") (pintype "input"))
    )
    (net (code "81") (name "Net-(U1-COMP)") (class "Default")
      (node (ref "C4") (pin "2") (pinfunction "2_2") (pintype "input"))
      (node (ref "C5") (pin "2") (pinfunction "2_2") (pintype "input"))
      (node (ref "U1") (pin "6") (pinfunction "COMP_6") (pintype "input"))
    )
    (net (code "82") (name "Net-(U1-FB)") (class "Default")
      (node (ref "R1") (pin "2") (pinfunction "2_2") (pintype "input"))
      (node (ref "R2") (pin "2") (pinfunction "2_2") (pintype "input"))
      (node (ref "U1") (pin "5") (pinfunction "FB_5") (pintype "input"))
    )
    (net (code "83") (name "Net-(U1-SS)") (class "Default")
      (node (ref "C3") (pin "2") (pinfunction "2_2") (pintype "input"))
      (node (ref "U1") (pin "8") (pinfunction "SS_8") (pintype "input"))
    )
    (net (code "84") (name "Net-(U2-RXD)") (class "Default")
      (node (ref "R5") (pin "2") (pinfunction "2_2") (pintype "input"))
      (node (ref "U2") (pin "3") (pinfunction "RXD_3") (pintype "input"))
    )
    (net (code "85") (name "Net-(U2-TXD)") (class "Default")
      (node (ref "R7") (pin "2") (pinfunction "2_2") (pintype "input"))
      (node (ref "U2") (pin "2") (pinfunction "TXD_2") (pintype "input"))
    )
    (net (code "86") (name "Net-(U4-OSCI)") (class "Default")
      (node (ref "U4") (pin "1") (pinfunction "OSCI_1") (pintype "input"))
      (node (ref "X2") (pin "2") (pinfunction "OSC2_2") (pintype "input"))
    )
    (net (code "87") (name "Net-(U4-OSCO)") (class "Default")
      (node (ref "C14") (pin "2") (pinfunction "2_2") (pintype "input"))
      (node (ref "U4") (pin "2") (pinfunction "OSCO_2") (pintype "input"))
      (node (ref "X2") (pin "1") (pinfunction "OSC1_1") (pintype "input"))
    )
    (net (code "88") (name "Net-(U4-VDD)") (class "Default")
      (node (ref "C15") (pin "1") (pinfunction "1_1") (pintype "input"))
      (node (ref "D2") (pin "1") (pinfunction "1_1") (pintype "input"))
      (node (ref "D3") (pin "1") (pinfunction "1_1") (pintype "input"))
      (node (ref "U4") (pin "8") (pinfunction "VDD_8") (pintype "input"))
    )
    (net (code "89") (name "Net-(U5-Q0)") (class "Default")
      (node (ref "R13") (pin "1") (pinfunction "1_1") (pintype "input"))
      (node (ref "U5") (pin "19") (pinfunction "Q0_19") (pintype "input"))
    )
    (net (code "90") (name "Net-(U5-Q1)") (class "Default")
      (node (ref "R14") (pin "1") (pinfunction "1_1") (pintype "input"))
      (node (ref "U5") (pin "18") (pinfunction "Q1_18") (pintype "input"))
    )
    (net (code "91") (name "Net-(U5-Q2)") (class "Default")
      (node (ref "R15") (pin "1") (pinfunction "1_1") (pintype "input"))
      (node (ref "U5") (pin "17") (pinfunction "Q2_17") (pintype "input"))
    )
    (net (code "92") (name "Net-(U5-Q3)") (class "Default")
      (node (ref "R16") (pin "1") (pinfunction "1_1") (pintype "input"))
      (node (ref "U5") (pin "16") (pinfunction "Q3_16") (pintype "input"))
    )
    (net (code "93") (name "Net-(U5-Q4)") (class "Default")
      (node (ref "R17") (pin "1") (pinfunction "1_1") (pintype "input"))
      (node (ref "U5") (pin "15") (pinfunction "Q4_15") (pintype "input"))
    )
    (net (code "94") (name "Net-(U5-Q5)") (class "Default")
      (node (ref "R18") (pin "1") (pinfunction "1_1") (pintype "input"))
      (node (ref "U5") (pin "14") (pinfunction "Q5_14") (pintype "input"))
    )
    (net (code "95") (name "Net-(U5-Q6)") (class "Default")
      (node (ref "R19") (pin "1") (pinfunction "1_1") (pintype "input"))
      (node (ref "U5") (pin "13") (pinfunction "Q6_13") (pintype "input"))
    )
    (net (code "96") (name "Net-(U5-Q7)") (class "Default")
      (node (ref "R20") (pin "1") (pinfunction "1_1") (pintype "input"))
      (node (ref "U5") (pin "12") (pinfunction "Q7_12") (pintype "input"))
    )
    (net (code "97") (name "Net-(U10-P1.0{slash}ADC0{slash}CCP1{slash}RXD2)") (class "Default")
      (node (ref "C21") (pin "1") (pinfunction "1_1") (pintype "input"))
      (node (ref "R22") (pin "2") (pinfunction "2_2") (pintype "input"))
      (node (ref "U10") (pin "4") (pinfunction "P1.0/ADC0/CCP1/RXD2_4") (pintype "input"))
    )
    (net (code "98") (name "Net-(U10-P1.1{slash}ADC1{slash}CCP0{slash}TXD2)") (class "Default")
      (node (ref "C22") (pin "1") (pinfunction "1_1") (pintype "input"))
      (node (ref "R21") (pin "2") (pinfunction "2_2") (pintype "input"))
      (node (ref "U10") (pin "5") (pinfunction "P1.1/ADC1/CCP0/TXD2_5") (pintype "input"))
    )
    (net (code "99") (name "Net-(U10-P1.2{slash}ADC2{slash}SS{slash}ECI)") (class "Default")
      (node (ref "C23") (pin "1") (pinfunction "1_1") (pintype "input"))
      (node (ref "R26") (pin "2") (pinfunction "2_2") (pintype "input"))
      (node (ref "U10") (pin "7") (pinfunction "P1.2/ADC2/SS/ECI_7") (pintype "input"))
    )
    (net (code "100") (name "Net-(U10-P1.3{slash}ADC3{slash}MOSI)") (class "Default")
      (node (ref "C24") (pin "1") (pinfunction "1_1") (pintype "input"))
      (node (ref "R27") (pin "2") (pinfunction "2_2") (pintype "input"))
      (node (ref "U10") (pin "8") (pinfunction "P1.3/ADC3/MOSI_8") (pintype "input"))
    )
    (net (code "101") (name "Net-(U10-P2.2{slash}MISO_2)") (class "Default")
      (node (ref "R6") (pin "1") (pinfunction "1_1") (pintype "input"))
      (node (ref "U10") (pin "32") (pinfunction "P2.2/MISO_2_32") (pintype "bidirectional"))
    )
    (net (code "102") (name "Net-(U10-P2.3{slash}MOSI_2)") (class "Default")
      (node (ref "R8") (pin "1") (pinfunction "1_1") (pintype "input"))
      (node (ref "U10") (pin "33") (pinfunction "P2.3/MOSI_2_33") (pintype "bidirectional"))
    )
    (net (code "103") (name "Net-(U10-P2.4{slash}ECI_3{slash}SS_2)") (class "Default")
      (node (ref "R9") (pin "1") (pinfunction "1_1") (pintype "input"))
      (node (ref "U10") (pin "34") (pinfunction "P2.4/ECI_3/SS_2_34") (pintype "bidirectional"))
    )
    (net (code "104") (name "Net-(U10-P2.5{slash}CCP0_3)") (class "Default")
      (node (ref "R10") (pin "1") (pinfunction "1_1") (pintype "input"))
      (node (ref "U10") (pin "35") (pinfunction "P2.5/CCP0_3_35") (pintype "bidirectional"))
    )
    (net (code "105") (name "Net-(U10-P2.6{slash}CCP1_3)") (class "Default")
      (node (ref "R11") (pin "1") (pinfunction "1_1") (pintype "input"))
      (node (ref "U10") (pin "36") (pinfunction "P2.6/CCP1_3_36") (pintype "bidirectional"))
    )
    (net (code "106") (name "Net-(U10-P2.7{slash}CCP2_3)") (class "Default")
      (node (ref "R12") (pin "1") (pinfunction "1_1") (pintype "input"))
      (node (ref "U10") (pin "37") (pinfunction "P2.7/CCP2_3_37") (pintype "bidirectional"))
    )
    (net (code "107") (name "Net-(USB1-VCC)") (class "Default")
      (node (ref "F1") (pin "1") (pinfunction "1_1") (pintype "input"))
      (node (ref "USB1") (pin "1") (pinfunction "VCC_1") (pintype "input"))
    )
    (net (code "108") (name "VUSB") (class "Default")
      (node (ref "C54") (pin "1") (pinfunction "1_1") (pintype "input"))
      (node (ref "F1") (pin "2") (pinfunction "2_2") (pintype "input"))
      (node (ref "U18") (pin "2") (pinfunction "VIN_2") (pintype "input"))
    )
    (net (code "109") (name "unconnected-(CN3-Pad7)") (class "Default")
      (node (ref "CN3") (pin "7") (pinfunction "7_7") (pintype "input+no_connect"))
    )
    (net (code "110") (name "unconnected-(U1-EN-Pad7)") (class "Default")
      (node (ref "U1") (pin "7") (pinfunction "EN_7") (pintype "input+no_connect"))
    )
    (net (code "111") (name "unconnected-(U2-CTS#-Pad9)") (class "Default")
      (node (ref "U2") (pin "9") (pinfunction "CTS#_9") (pintype "input+no_connect"))
    )
    (net (code "112") (name "unconnected-(U2-DCD#-Pad12)") (class "Default")
      (node (ref "U2") (pin "12") (pinfunction "DCD#_12") (pintype "input+no_connect"))
    )
    (net (code "113") (name "unconnected-(U2-DSR#-Pad10)") (class "Default")
      (node (ref "U2") (pin "10") (pinfunction "DSR#_10") (pintype "input+no_connect"))
    )
    (net (code "114") (name "unconnected-(U2-DTR#-Pad13)") (class "Default")
      (node (ref "U2") (pin "13") (pinfunction "DTR#_13") (pintype "input+no_connect"))
    )
    (net (code "115") (name "unconnected-(U2-NC.-Pad7)") (class "Default")
      (node (ref "U2") (pin "7") (pinfunction "NC._7") (pintype "input+no_connect"))
    )
    (net (code "116") (name "unconnected-(U2-NC.-Pad8)") (class "Default")
      (node (ref "U2") (pin "8") (pinfunction "NC._8") (pintype "input+no_connect"))
    )
    (net (code "117") (name "unconnected-(U2-R232-Pad15)") (class "Default")
      (node (ref "U2") (pin "15") (pinfunction "R232_15") (pintype "input+no_connect"))
    )
    (net (code "118") (name "unconnected-(U2-RI#-Pad11)") (class "Default")
      (node (ref "U2") (pin "11") (pinfunction "RI#_11") (pintype "input+no_connect"))
    )
    (net (code "119") (name "unconnected-(U2-RTS#-Pad14)") (class "Default")
      (node (ref "U2") (pin "14") (pinfunction "RTS#_14") (pintype "input+no_connect"))
    )
    (net (code "120") (name "unconnected-(U4-CLKOUT-Pad7)") (class "Default")
      (node (ref "U4") (pin "7") (pinfunction "CLKOUT_7") (pintype "input+no_connect"))
    )
    (net (code "121") (name "unconnected-(U4-INT#-Pad3)") (class "Default")
      (node (ref "U4") (pin "3") (pinfunction "INT#_3") (pintype "input+no_connect"))
    )
    (net (code "122") (name "unconnected-(U10-P1.6{slash}ADC6{slash}RXD_3{slash}XTAL2-Pad11)") (class "Default")
      (node (ref "U10") (pin "11") (pinfunction "P1.6/ADC6/RXD_3/XTAL2_11") (pintype "bidirectional+no_connect"))
    )
    (net (code "123") (name "unconnected-(U10-P1.7{slash}ADC7{slash}TXD_3{slash}XTAL1-Pad12)") (class "Default")
      (node (ref "U10") (pin "12") (pinfunction "P1.7/ADC7/TXD_3/XTAL1_12") (pintype "bidirectional+no_connect"))
    )
    (net (code "124") (name "unconnected-(U10-P5.4{slash}RST{slash}MCLK0{slash}SS_3-Pad13)") (class "Default")
      (node (ref "U10") (pin "13") (pinfunction "P5.4/RST/MCLK0/SS_3_13") (pintype "input+no_connect"))
    )
  )
)
